# epic.net
KiCad netlist of a schematic drawn in Altium Designer
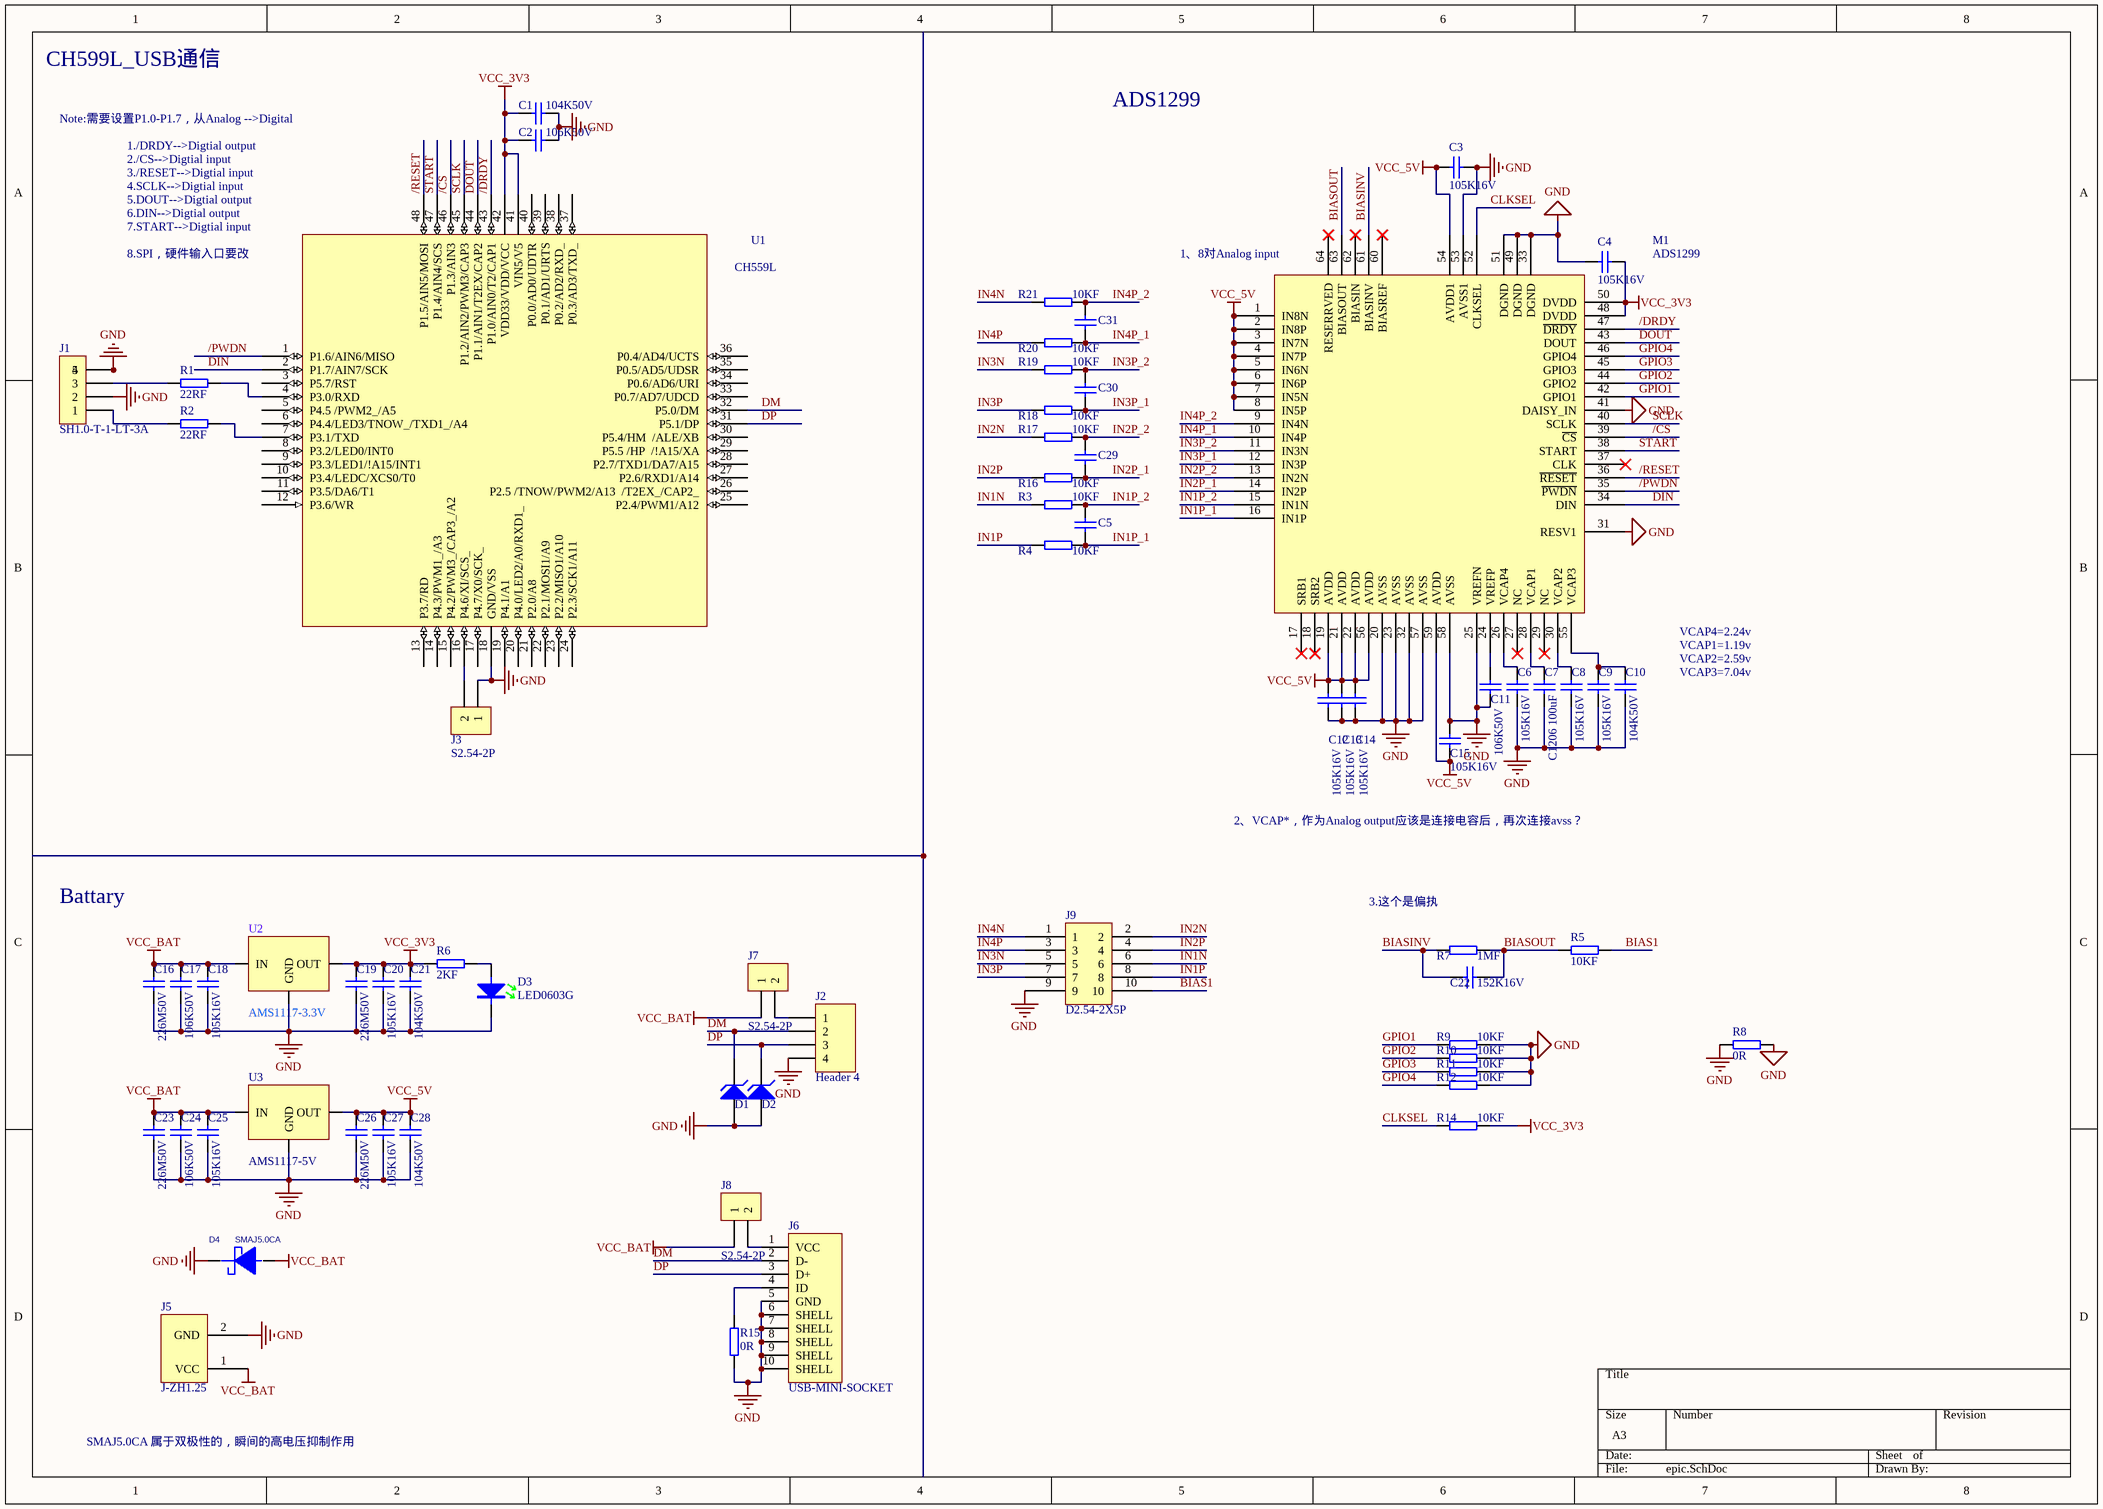
[diagram p0: epic.SchDoc]

(export (version "E")
  (design (tool "Eeschema 10.0.6"))
  (components
    (comp (ref "C1")
      (value "104K50V")
      (footprint "C0603")
      (description "贴片电容-陶瓷")
      (libsource (lib "Capacitor") (part "C0603X7R-104K50V"))
    )
    (comp (ref "C2")
      (value "106K50V")
      (footprint "C0603")
      (description "贴片电容-陶瓷")
      (libsource (lib "Capacitor") (part "C0603X7R-106K50V"))
    )
    (comp (ref "C3")
      (value "105K16V")
      (footprint "C0603")
      (description "贴片电容-陶瓷")
      (libsource (lib "Capacitor") (part "C0603X7R-105K16V"))
    )
    (comp (ref "C4")
      (value "105K16V")
      (footprint "C0603")
      (description "贴片电容-陶瓷")
      (libsource (lib "Capacitor") (part "C0603X7R-105K16V"))
    )
    (comp (ref "C5")
      (value "101K10V")
      (footprint "C0603")
      (description "贴片电容-陶瓷")
      (libsource (lib "Capacitor") (part "C0603X7R-101K10V"))
    )
    (comp (ref "C6")
      (value "105K16V")
      (footprint "C0603")
      (description "贴片电容-陶瓷")
      (libsource (lib "Capacitor") (part "C0603X7R-105K16V"))
    )
    (comp (ref "C7")
      (value "C1206 100uF")
      (footprint "C1206")
      (libsource (lib "Capacitor") (part "C1206钽电容 --100UF"))
    )
    (comp (ref "C8")
      (value "105K16V")
      (footprint "C0603")
      (description "贴片电容-陶瓷")
      (libsource (lib "Capacitor") (part "C0603X7R-105K16V"))
    )
    (comp (ref "C9")
      (value "105K16V")
      (footprint "C0603")
      (description "贴片电容-陶瓷")
      (libsource (lib "Capacitor") (part "C0603X7R-105K16V"))
    )
    (comp (ref "C10")
      (value "104K50V")
      (footprint "C0603")
      (description "贴片电容-陶瓷")
      (libsource (lib "Capacitor") (part "C0603X7R-104K50V"))
    )
    (comp (ref "C11")
      (value "106K50V")
      (footprint "C0603")
      (description "贴片电容-陶瓷")
      (libsource (lib "Capacitor") (part "C0603X7R-106K50V"))
    )
    (comp (ref "C12")
      (value "105K16V")
      (footprint "C0603")
      (description "贴片电容-陶瓷")
      (libsource (lib "Capacitor") (part "C0603X7R-105K16V"))
    )
    (comp (ref "C13")
      (value "105K16V")
      (footprint "C0603")
      (description "贴片电容-陶瓷")
      (libsource (lib "Capacitor") (part "C0603X7R-105K16V"))
    )
    (comp (ref "C14")
      (value "105K16V")
      (footprint "C0603")
      (description "贴片电容-陶瓷")
      (libsource (lib "Capacitor") (part "C0603X7R-105K16V"))
    )
    (comp (ref "C15")
      (value "105K16V")
      (footprint "C0603")
      (description "贴片电容-陶瓷")
      (libsource (lib "Capacitor") (part "C0603X7R-105K16V"))
    )
    (comp (ref "C16")
      (value "226M50V")
      (footprint "C0805")
      (description "贴片电容-陶瓷")
      (libsource (lib "aiwacV2.0") (part "C0805Y5V-226M50V"))
    )
    (comp (ref "C17")
      (value "106K50V")
      (footprint "C0603")
      (description "贴片电容-陶瓷")
      (libsource (lib "aiwacV2.0") (part "C0603X7R-106K50V"))
    )
    (comp (ref "C18")
      (value "105K16V")
      (footprint "C0603")
      (description "贴片电容-陶瓷")
      (libsource (lib "aiwacV2.0") (part "C0603X7R-105K16V"))
    )
    (comp (ref "C19")
      (value "226M50V")
      (footprint "C0805")
      (description "贴片电容-陶瓷")
      (libsource (lib "aiwacV2.0") (part "C0805Y5V-226M50V"))
    )
    (comp (ref "C20")
      (value "105K16V")
      (footprint "C0603")
      (description "贴片电容-陶瓷")
      (libsource (lib "aiwacV2.0") (part "C0603X7R-105K16V"))
    )
    (comp (ref "C21")
      (value "104K50V")
      (footprint "C0603")
      (description "贴片电容-陶瓷")
      (libsource (lib "Capacitor") (part "C0603X7R-104K50V"))
    )
    (comp (ref "C22")
      (value "152K16V")
      (footprint "C0603")
      (description "贴片电容-陶瓷")
      (libsource (lib "Capacitor") (part "C0603X7R-152K16V"))
    )
    (comp (ref "C23")
      (value "226M50V")
      (footprint "C0805")
      (description "贴片电容-陶瓷")
      (libsource (lib "aiwacV2.0") (part "C0805Y5V-226M50V"))
    )
    (comp (ref "C24")
      (value "106K50V")
      (footprint "C0603")
      (description "贴片电容-陶瓷")
      (libsource (lib "aiwacV2.0") (part "C0603X7R-106K50V"))
    )
    (comp (ref "C25")
      (value "105K16V")
      (footprint "C0603")
      (description "贴片电容-陶瓷")
      (libsource (lib "aiwacV2.0") (part "C0603X7R-105K16V"))
    )
    (comp (ref "C26")
      (value "226M50V")
      (footprint "C0805")
      (description "贴片电容-陶瓷")
      (libsource (lib "aiwacV2.0") (part "C0805Y5V-226M50V"))
    )
    (comp (ref "C27")
      (value "105K16V")
      (footprint "C0603")
      (description "贴片电容-陶瓷")
      (libsource (lib "aiwacV2.0") (part "C0603X7R-105K16V"))
    )
    (comp (ref "C28")
      (value "104K50V")
      (footprint "C0603")
      (description "贴片电容-陶瓷")
      (libsource (lib "Capacitor") (part "C0603X7R-104K50V"))
    )
    (comp (ref "C29")
      (value "101K10V")
      (footprint "C0603")
      (description "贴片电容-陶瓷")
      (libsource (lib "Capacitor") (part "C0603X7R-101K10V"))
    )
    (comp (ref "C30")
      (value "101K10V")
      (footprint "C0603")
      (description "贴片电容-陶瓷")
      (libsource (lib "Capacitor") (part "C0603X7R-101K10V"))
    )
    (comp (ref "C31")
      (value "101K10V")
      (footprint "C0603")
      (description "贴片电容-陶瓷")
      (libsource (lib "Capacitor") (part "C0603X7R-101K10V"))
    )
    (comp (ref "D1")
      (value "ESDA_TR1/0603")
      (footprint "HS_0603D")
      (description "Zener Diode")
      (fields (field (name "PUBLISHER") "*"))
      (libsource (lib "aiwacV2.0") (part "D Zener"))
    )
    (comp (ref "D2")
      (value "ESDA_TR1/0603")
      (footprint "HS_0603D")
      (description "Zener Diode")
      (fields (field (name "PUBLISHER") "*"))
      (libsource (lib "aiwacV2.0") (part "D Zener"))
    )
    (comp (ref "D3")
      (value "LED0603G")
      (footprint "D-LED0603G")
      (description "贴片二极管-LED")
      (libsource (lib "aiwacV2.0") (part "DLED-0603-G"))
    )
    (comp (ref "D4")
      (value "SMAJ5.0CA")
      (footprint "PCB11:DO-214")
      (libsource (lib "aiwacV2.0") (part "SMAJ5.0CA"))
    )
    (comp (ref "J1")
      (value "SH1.0-T-1-LT-3A")
      (footprint "AIWAC-TF_CARD-V02:J-SH1.0-T-1-LT-3A")
      (description "接插件-SH1.0-T-1-LT-3A")
      (libsource (lib "aiwacV2.0") (part "SH1.0-T-1-LT-3A"))
    )
    (comp (ref "J2")
      (value "Header 4")
      (footprint "USB-AB")
      (description "Header, 4-Pin")
      (fields (field (name "PUBLISHER") "Altium Limited"))
      (libsource (lib "aiwacV2.0") (part "Header 4"))
    )
    (comp (ref "J3")
      (value "S2.54-2P")
      (footprint "S2.54-2P")
      (description "单排排针-直针")
      (libsource (lib "") (part "J-S2.54-2P_1"))
    )
    (comp (ref "J5")
      (value "J-ZH1.25")
      (footprint "ZH1.25_2P")
      (libsource (lib "Connector") (part "J-ZH1.25"))
    )
    (comp (ref "J6")
      (value "USB-MINI-SOCKET")
      (footprint "MICRO-USB - 5.9")
      (description "USB-A卧式插座")
      (libsource (lib "PCB_Project_1") (part "J-USB-MINI-SOCKET"))
    )
    (comp (ref "J7")
      (value "S2.54-2P")
      (footprint "S2.54-2P")
      (description "单排排针-直针")
      (libsource (lib "Connector") (part "J-S2.54-2P"))
    )
    (comp (ref "J8")
      (value "S2.54-2P")
      (footprint "S2.54-2P")
      (description "单排排针-直针")
      (libsource (lib "Connector") (part "J-S2.54-2P"))
    )
    (comp (ref "J9")
      (value "D2.54-2X5P")
      (footprint "D2.54-2X5P")
      (description "双排排针-直针")
      (libsource (lib "Connector") (part "J-D2.54-2X5P"))
    )
    (comp (ref "M1")
      (value "ADS1299")
      (footprint "ADS1299-TSQFP50P1200X1200X105-64N")
      (description "ADS1299-S-PQFP-64")
      (libsource (lib "epic") (part "ADS1299"))
    )
    (comp (ref "R1")
      (value "22RF")
      (footprint "R0603")
      (description "贴片电阻-通用")
      (libsource (lib "Resistor") (part "R0603-22RF"))
    )
    (comp (ref "R2")
      (value "22RF")
      (footprint "R0603")
      (description "贴片电阻-通用")
      (libsource (lib "Resistor") (part "R0603-22RF"))
    )
    (comp (ref "R3")
      (value "10KF")
      (footprint "R0603")
      (description "贴片电阻-通用")
      (libsource (lib "Resistor") (part "R0603-10KF"))
    )
    (comp (ref "R4")
      (value "10KF")
      (footprint "R0603")
      (description "贴片电阻-通用")
      (libsource (lib "Resistor") (part "R0603-10KF"))
    )
    (comp (ref "R5")
      (value "10KF")
      (footprint "R0603")
      (description "贴片电阻-通用")
      (libsource (lib "Resistor") (part "R0603-10KF"))
    )
    (comp (ref "R6")
      (value "2KF")
      (footprint "R0603")
      (description "贴片电阻-通用")
      (libsource (lib "Resistor") (part "R0603-2KF"))
    )
    (comp (ref "R7")
      (value "1MF")
      (footprint "R0603")
      (description "贴片电阻-通用")
      (libsource (lib "Resistor") (part "R0603-1MF"))
    )
    (comp (ref "R8")
      (value "0R")
      (footprint "R0603")
      (description "贴片电阻-通用")
      (libsource (lib "Resistor") (part "R0603-0R"))
    )
    (comp (ref "R9")
      (value "10KF")
      (footprint "R0603")
      (description "贴片电阻-通用")
      (libsource (lib "Resistor") (part "R0603-10KF"))
    )
    (comp (ref "R10")
      (value "10KF")
      (footprint "R0603")
      (description "贴片电阻-通用")
      (libsource (lib "Resistor") (part "R0603-10KF"))
    )
    (comp (ref "R11")
      (value "10KF")
      (footprint "R0603")
      (description "贴片电阻-通用")
      (libsource (lib "Resistor") (part "R0603-10KF"))
    )
    (comp (ref "R12")
      (value "10KF")
      (footprint "R0603")
      (description "贴片电阻-通用")
      (libsource (lib "Resistor") (part "R0603-10KF"))
    )
    (comp (ref "R14")
      (value "10KF")
      (footprint "R0603")
      (description "贴片电阻-通用")
      (libsource (lib "Resistor") (part "R0603-10KF"))
    )
    (comp (ref "R15")
      (value "0R")
      (footprint "R0603")
      (description "贴片电阻-通用")
      (libsource (lib "Resistor") (part "R0603-0R"))
    )
    (comp (ref "R16")
      (value "10KF")
      (footprint "R0603")
      (description "贴片电阻-通用")
      (libsource (lib "Resistor") (part "R0603-10KF"))
    )
    (comp (ref "R17")
      (value "10KF")
      (footprint "R0603")
      (description "贴片电阻-通用")
      (libsource (lib "Resistor") (part "R0603-10KF"))
    )
    (comp (ref "R18")
      (value "10KF")
      (footprint "R0603")
      (description "贴片电阻-通用")
      (libsource (lib "Resistor") (part "R0603-10KF"))
    )
    (comp (ref "R19")
      (value "10KF")
      (footprint "R0603")
      (description "贴片电阻-通用")
      (libsource (lib "Resistor") (part "R0603-10KF"))
    )
    (comp (ref "R20")
      (value "10KF")
      (footprint "R0603")
      (description "贴片电阻-通用")
      (libsource (lib "Resistor") (part "R0603-10KF"))
    )
    (comp (ref "R21")
      (value "10KF")
      (footprint "R0603")
      (description "贴片电阻-通用")
      (libsource (lib "Resistor") (part "R0603-10KF"))
    )
    (comp (ref "U1")
      (value "CH559L")
      (footprint "LQFP48")
      (description "单片机")
      (libsource (lib "aiwacV2.0") (part "CH559L"))
    )
    (comp (ref "U2")
      (value "AMS1117-3.3V")
      (footprint "SOT-223")
      (description "芯片 电源类")
      (libsource (lib "aiwacV2.0") (part "AP1117-33 SOT-223"))
    )
    (comp (ref "U3")
      (value "AMS1117-5V")
      (footprint "SOT-223")
      (description "线性稳压器")
      (libsource (lib "epic") (part "AMS1117-5V"))
    )
  )
  (nets
    (net (code "1") (name "/BIAS1") (class "Default")
      (node (ref "J9") (pin "10") (pinfunction "10_10") (pintype "passive"))
      (node (ref "R5") (pin "2") (pinfunction "2_2") (pintype "passive"))
    )
    (net (code "2") (name "/BIASINV") (class "Default")
      (node (ref "C22") (pin "2") (pinfunction "2_2") (pintype "passive"))
      (node (ref "M1") (pin "61") (pinfunction "BIASINV_61") (pintype "passive"))
      (node (ref "R7") (pin "1") (pinfunction "1_1") (pintype "passive"))
    )
    (net (code "3") (name "/BIASOUT") (class "Default")
      (node (ref "C22") (pin "1") (pinfunction "1_1") (pintype "passive"))
      (node (ref "M1") (pin "63") (pinfunction "BIASOUT_63") (pintype "passive"))
      (node (ref "R5") (pin "1") (pinfunction "1_1") (pintype "passive"))
      (node (ref "R7") (pin "2") (pinfunction "2_2") (pintype "passive"))
    )
    (net (code "4") (name "/CLKSEL") (class "Default")
      (node (ref "M1") (pin "52") (pinfunction "CLKSEL_52") (pintype "passive"))
      (node (ref "R14") (pin "1") (pinfunction "1_1") (pintype "passive"))
    )
    (net (code "5") (name "/DIN") (class "Default")
      (node (ref "M1") (pin "34") (pinfunction "DIN_34") (pintype "passive"))
      (node (ref "U1") (pin "2") (pinfunction "P1.7/AIN7/SCK_2") (pintype "bidirectional"))
    )
    (net (code "6") (name "/DM") (class "Default")
      (node (ref "D1") (pin "2") (pinfunction "K_2") (pintype "passive"))
      (node (ref "J2") (pin "2") (pinfunction "2_2") (pintype "passive"))
      (node (ref "J6") (pin "2") (pinfunction "D-_2") (pintype "passive"))
      (node (ref "U1") (pin "32") (pinfunction "P5.0/DM_32") (pintype "bidirectional"))
    )
    (net (code "7") (name "/DOUT") (class "Default")
      (node (ref "M1") (pin "43") (pinfunction "DOUT_43") (pintype "passive"))
      (node (ref "U1") (pin "44") (pinfunction "P1.1/AIN1/T2EX/CAP2_44") (pintype "bidirectional"))
    )
    (net (code "8") (name "/DP") (class "Default")
      (node (ref "D2") (pin "2") (pinfunction "K_2") (pintype "passive"))
      (node (ref "J2") (pin "3") (pinfunction "3_3") (pintype "passive"))
      (node (ref "J6") (pin "3") (pinfunction "D+_3") (pintype "passive"))
      (node (ref "U1") (pin "31") (pinfunction "P5.1/DP_31") (pintype "bidirectional"))
    )
    (net (code "9") (name "/GPIO1") (class "Default")
      (node (ref "M1") (pin "42") (pinfunction "GPIO1_42") (pintype "passive"))
      (node (ref "R9") (pin "1") (pinfunction "1_1") (pintype "passive"))
    )
    (net (code "10") (name "/GPIO2") (class "Default")
      (node (ref "M1") (pin "44") (pinfunction "GPIO2_44") (pintype "passive"))
      (node (ref "R10") (pin "1") (pinfunction "1_1") (pintype "passive"))
    )
    (net (code "11") (name "/GPIO3") (class "Default")
      (node (ref "M1") (pin "45") (pinfunction "GPIO3_45") (pintype "passive"))
      (node (ref "R11") (pin "1") (pinfunction "1_1") (pintype "passive"))
    )
    (net (code "12") (name "/GPIO4") (class "Default")
      (node (ref "M1") (pin "46") (pinfunction "GPIO4_46") (pintype "passive"))
      (node (ref "R12") (pin "1") (pinfunction "1_1") (pintype "passive"))
    )
    (net (code "13") (name "/IN1N") (class "Default")
      (node (ref "J9") (pin "6") (pinfunction "6_6") (pintype "passive"))
      (node (ref "R3") (pin "1") (pinfunction "1_1") (pintype "passive"))
    )
    (net (code "14") (name "/IN1P") (class "Default")
      (node (ref "J9") (pin "8") (pinfunction "8_8") (pintype "passive"))
      (node (ref "R4") (pin "1") (pinfunction "1_1") (pintype "passive"))
    )
    (net (code "15") (name "/IN1P_1") (class "Default")
      (node (ref "C5") (pin "2") (pinfunction "2_2") (pintype "passive"))
      (node (ref "M1") (pin "16") (pinfunction "IN1P_16") (pintype "passive"))
      (node (ref "R4") (pin "2") (pinfunction "2_2") (pintype "passive"))
    )
    (net (code "16") (name "/IN1P_2") (class "Default")
      (node (ref "C5") (pin "1") (pinfunction "1_1") (pintype "passive"))
      (node (ref "M1") (pin "15") (pinfunction "IN1N_15") (pintype "passive"))
      (node (ref "R3") (pin "2") (pinfunction "2_2") (pintype "passive"))
    )
    (net (code "17") (name "/IN2N") (class "Default")
      (node (ref "J9") (pin "2") (pinfunction "2_2") (pintype "passive"))
      (node (ref "R17") (pin "1") (pinfunction "1_1") (pintype "passive"))
    )
    (net (code "18") (name "/IN2P") (class "Default")
      (node (ref "J9") (pin "4") (pinfunction "4_4") (pintype "passive"))
      (node (ref "R16") (pin "1") (pinfunction "1_1") (pintype "passive"))
    )
    (net (code "19") (name "/IN2P_1") (class "Default")
      (node (ref "C29") (pin "2") (pinfunction "2_2") (pintype "passive"))
      (node (ref "M1") (pin "14") (pinfunction "IN2P_14") (pintype "passive"))
      (node (ref "R16") (pin "2") (pinfunction "2_2") (pintype "passive"))
    )
    (net (code "20") (name "/IN2P_2") (class "Default")
      (node (ref "C29") (pin "1") (pinfunction "1_1") (pintype "passive"))
      (node (ref "M1") (pin "13") (pinfunction "IN2N_13") (pintype "passive"))
      (node (ref "R17") (pin "2") (pinfunction "2_2") (pintype "passive"))
    )
    (net (code "21") (name "/IN3N") (class "Default")
      (node (ref "J9") (pin "5") (pinfunction "5_5") (pintype "passive"))
      (node (ref "R19") (pin "1") (pinfunction "1_1") (pintype "passive"))
    )
    (net (code "22") (name "/IN3P") (class "Default")
      (node (ref "J9") (pin "7") (pinfunction "7_7") (pintype "passive"))
      (node (ref "R18") (pin "1") (pinfunction "1_1") (pintype "passive"))
    )
    (net (code "23") (name "/IN3P_1") (class "Default")
      (node (ref "C30") (pin "2") (pinfunction "2_2") (pintype "passive"))
      (node (ref "M1") (pin "12") (pinfunction "IN3P_12") (pintype "passive"))
      (node (ref "R18") (pin "2") (pinfunction "2_2") (pintype "passive"))
    )
    (net (code "24") (name "/IN3P_2") (class "Default")
      (node (ref "C30") (pin "1") (pinfunction "1_1") (pintype "passive"))
      (node (ref "M1") (pin "11") (pinfunction "IN3N_11") (pintype "passive"))
      (node (ref "R19") (pin "2") (pinfunction "2_2") (pintype "passive"))
    )
    (net (code "25") (name "/IN4N") (class "Default")
      (node (ref "J9") (pin "1") (pinfunction "1_1") (pintype "passive"))
      (node (ref "R21") (pin "1") (pinfunction "1_1") (pintype "passive"))
    )
    (net (code "26") (name "/IN4P") (class "Default")
      (node (ref "J9") (pin "3") (pinfunction "3_3") (pintype "passive"))
      (node (ref "R20") (pin "1") (pinfunction "1_1") (pintype "passive"))
    )
    (net (code "27") (name "/IN4P_1") (class "Default")
      (node (ref "C31") (pin "2") (pinfunction "2_2") (pintype "passive"))
      (node (ref "M1") (pin "10") (pinfunction "IN4P_10") (pintype "passive"))
      (node (ref "R20") (pin "2") (pinfunction "2_2") (pintype "passive"))
    )
    (net (code "28") (name "/IN4P_2") (class "Default")
      (node (ref "C31") (pin "1") (pinfunction "1_1") (pintype "passive"))
      (node (ref "M1") (pin "9") (pinfunction "IN4N_9") (pintype "passive"))
      (node (ref "R21") (pin "2") (pinfunction "2_2") (pintype "passive"))
    )
    (net (code "29") (name "/SCLK") (class "Default")
      (node (ref "M1") (pin "40") (pinfunction "SCLK_40") (pintype "passive"))
      (node (ref "U1") (pin "45") (pinfunction "P1.2/AIN2/PWM3/CAP3_45") (pintype "bidirectional"))
    )
    (net (code "30") (name "/START") (class "Default")
      (node (ref "M1") (pin "38") (pinfunction "START_38") (pintype "passive"))
      (node (ref "U1") (pin "47") (pinfunction "P1.4/AIN4/SCS_47") (pintype "bidirectional"))
    )
    (net (code "31") (name "/{slash}CS") (class "Default")
      (node (ref "M1") (pin "39") (pinfunction "~{CS}_39") (pintype "passive"))
      (node (ref "U1") (pin "46") (pinfunction "P1.3/AIN3_46") (pintype "bidirectional"))
    )
    (net (code "32") (name "/{slash}DRDY") (class "Default")
      (node (ref "M1") (pin "47") (pinfunction "~{DRDY}_47") (pintype "passive"))
      (node (ref "U1") (pin "43") (pinfunction "P1.0/AIN0/T2/CAP1_43") (pintype "bidirectional"))
    )
    (net (code "33") (name "/{slash}PWDN") (class "Default")
      (node (ref "M1") (pin "35") (pinfunction "~{PWDN}_35") (pintype "passive"))
      (node (ref "U1") (pin "1") (pinfunction "P1.6/AIN6/MISO_1") (pintype "bidirectional"))
    )
    (net (code "34") (name "/{slash}RESET") (class "Default")
      (node (ref "M1") (pin "36") (pinfunction "~{RESET}_36") (pintype "passive"))
      (node (ref "U1") (pin "48") (pinfunction "P1.5/AIN5/MOSI_48") (pintype "bidirectional"))
    )
    (net (code "35") (name "GND") (class "Default")
      (node (ref "C1") (pin "1") (pinfunction "1_1") (pintype "passive"))
      (node (ref "C10") (pin "1") (pinfunction "1_1") (pintype "passive"))
      (node (ref "C11") (pin "1") (pinfunction "1_1") (pintype "passive"))
      (node (ref "C12") (pin "2") (pinfunction "2_2") (pintype "passive"))
      (node (ref "C13") (pin "2") (pinfunction "2_2") (pintype "passive"))
      (node (ref "C14") (pin "2") (pinfunction "2_2") (pintype "passive"))
      (node (ref "C15") (pin "2") (pinfunction "2_2") (pintype "passive"))
      (node (ref "C16") (pin "2") (pinfunction "2_2") (pintype "passive"))
      (node (ref "C17") (pin "2") (pinfunction "2_2") (pintype "passive"))
      (node (ref "C18") (pin "2") (pinfunction "2_2") (pintype "passive"))
      (node (ref "C19") (pin "2") (pinfunction "2_2") (pintype "passive"))
      (node (ref "C2") (pin "1") (pinfunction "1_1") (pintype "passive"))
      (node (ref "C20") (pin "2") (pinfunction "2_2") (pintype "passive"))
      (node (ref "C21") (pin "1") (pinfunction "1_1") (pintype "passive"))
      (node (ref "C23") (pin "2") (pinfunction "2_2") (pintype "passive"))
      (node (ref "C24") (pin "2") (pinfunction "2_2") (pintype "passive"))
      (node (ref "C25") (pin "2") (pinfunction "2_2") (pintype "passive"))
      (node (ref "C26") (pin "2") (pinfunction "2_2") (pintype "passive"))
      (node (ref "C27") (pin "2") (pinfunction "2_2") (pintype "passive"))
      (node (ref "C28") (pin "1") (pinfunction "1_1") (pintype "passive"))
      (node (ref "C3") (pin "1") (pinfunction "1_1") (pintype "passive"))
      (node (ref "C4") (pin "1") (pinfunction "1_1") (pintype "passive"))
      (node (ref "C6") (pin "2") (pinfunction "2_2") (pintype "passive"))
      (node (ref "C7") (pin "1") (pinfunction "1_1") (pintype "passive"))
      (node (ref "C8") (pin "2") (pinfunction "2_2") (pintype "passive"))
      (node (ref "C9") (pin "2") (pinfunction "2_2") (pintype "passive"))
      (node (ref "D1") (pin "1") (pinfunction "A_1") (pintype "passive"))
      (node (ref "D2") (pin "1") (pinfunction "A_1") (pintype "passive"))
      (node (ref "D3") (pin "2") (pinfunction "2_2") (pintype "passive"))
      (node (ref "D4") (pin "2") (pinfunction "-_2") (pintype "passive"))
      (node (ref "J1") (pin "2") (pinfunction "2_2") (pintype "passive"))
      (node (ref "J1") (pin "4") (pinfunction "4_4") (pintype "passive"))
      (node (ref "J1") (pin "5") (pinfunction "5_5") (pintype "passive"))
      (node (ref "J2") (pin "4") (pinfunction "4_4") (pintype "passive"))
      (node (ref "J3") (pin "1") (pinfunction "1_1") (pintype "passive"))
      (node (ref "J5") (pin "2") (pinfunction "GND_2") (pintype "power_in"))
      (node (ref "J6") (pin "10") (pinfunction "SHELL_10") (pintype "passive"))
      (node (ref "J6") (pin "5") (pinfunction "GND_5") (pintype "passive"))
      (node (ref "J6") (pin "6") (pinfunction "SHELL_6") (pintype "passive"))
      (node (ref "J6") (pin "7") (pinfunction "SHELL_7") (pintype "passive"))
      (node (ref "J6") (pin "8") (pinfunction "SHELL_8") (pintype "passive"))
      (node (ref "J6") (pin "9") (pinfunction "SHELL_9") (pintype "passive"))
      (node (ref "J9") (pin "9") (pinfunction "9_9") (pintype "passive"))
      (node (ref "M1") (pin "20") (pinfunction "AVSS_20") (pintype "passive"))
      (node (ref "M1") (pin "23") (pinfunction "AVSS_23") (pintype "passive"))
      (node (ref "M1") (pin "25") (pinfunction "VREFN_25") (pintype "passive"))
      (node (ref "M1") (pin "31") (pinfunction "RESV1_31") (pintype "passive"))
      (node (ref "M1") (pin "32") (pinfunction "AVSS_32") (pintype "passive"))
      (node (ref "M1") (pin "33") (pinfunction "DGND_33") (pintype "passive"))
      (node (ref "M1") (pin "41") (pinfunction "DAISY_IN_41") (pintype "passive"))
      (node (ref "M1") (pin "49") (pinfunction "DGND_49") (pintype "passive"))
      (node (ref "M1") (pin "51") (pinfunction "DGND_51") (pintype "passive"))
      (node (ref "M1") (pin "53") (pinfunction "AVSS1_53") (pintype "passive"))
      (node (ref "M1") (pin "57") (pinfunction "AVSS_57") (pintype "passive"))
      (node (ref "M1") (pin "58") (pinfunction "AVSS_58") (pintype "passive"))
      (node (ref "R10") (pin "2") (pinfunction "2_2") (pintype "passive"))
      (node (ref "R11") (pin "2") (pinfunction "2_2") (pintype "passive"))
      (node (ref "R12") (pin "2") (pinfunction "2_2") (pintype "passive"))
      (node (ref "R15") (pin "1") (pinfunction "1_1") (pintype "passive"))
      (node (ref "R8") (pin "1") (pinfunction "1_1") (pintype "passive"))
      (node (ref "R8") (pin "2") (pinfunction "2_2") (pintype "passive"))
      (node (ref "R9") (pin "2") (pinfunction "2_2") (pintype "passive"))
      (node (ref "U1") (pin "18") (pinfunction "GND/VSS_18") (pintype "passive"))
      (node (ref "U2") (pin "1") (pinfunction "GND_1") (pintype "passive"))
      (node (ref "U3") (pin "1") (pinfunction "GND_1") (pintype "passive"))
    )
    (net (code "36") (name "Net-(D3-Pad1)") (class "Default")
      (node (ref "D3") (pin "1") (pinfunction "1_1") (pintype "passive"))
      (node (ref "R6") (pin "2") (pinfunction "2_2") (pintype "passive"))
    )
    (net (code "37") (name "Net-(J1-Pad1)") (class "Default")
      (node (ref "J1") (pin "1") (pinfunction "1_1") (pintype "passive"))
      (node (ref "R2") (pin "1") (pinfunction "1_1") (pintype "passive"))
    )
    (net (code "38") (name "Net-(J1-Pad3)") (class "Default")
      (node (ref "J1") (pin "3") (pinfunction "3_3") (pintype "passive"))
      (node (ref "R1") (pin "1") (pinfunction "1_1") (pintype "passive"))
    )
    (net (code "39") (name "Net-(J2-Pad1)") (class "Default")
      (node (ref "J2") (pin "1") (pinfunction "1_1") (pintype "passive"))
      (node (ref "J7") (pin "2") (pinfunction "2_2") (pintype "passive"))
    )
    (net (code "40") (name "Net-(J6-ID)") (class "Default")
      (node (ref "J6") (pin "4") (pinfunction "ID_4") (pintype "passive"))
      (node (ref "R15") (pin "2") (pinfunction "2_2") (pintype "passive"))
    )
    (net (code "41") (name "Net-(J6-VCC)") (class "Default")
      (node (ref "J6") (pin "1") (pinfunction "VCC_1") (pintype "passive"))
      (node (ref "J8") (pin "2") (pinfunction "2_2") (pintype "passive"))
    )
    (net (code "42") (name "Net-(M1-VCAP1)") (class "Default")
      (node (ref "C7") (pin "2") (pinfunction "2_2") (pintype "passive"))
      (node (ref "M1") (pin "28") (pinfunction "VCAP1_28") (pintype "passive"))
    )
    (net (code "43") (name "Net-(M1-VCAP2)") (class "Default")
      (node (ref "C8") (pin "1") (pinfunction "1_1") (pintype "passive"))
      (node (ref "M1") (pin "30") (pinfunction "VCAP2_30") (pintype "passive"))
    )
    (net (code "44") (name "Net-(M1-VCAP3)") (class "Default")
      (node (ref "C10") (pin "2") (pinfunction "2_2") (pintype "passive"))
      (node (ref "C9") (pin "1") (pinfunction "1_1") (pintype "passive"))
      (node (ref "M1") (pin "55") (pinfunction "VCAP3_55") (pintype "passive"))
    )
    (net (code "45") (name "Net-(M1-VCAP4)") (class "Default")
      (node (ref "C6") (pin "1") (pinfunction "1_1") (pintype "passive"))
      (node (ref "M1") (pin "26") (pinfunction "VCAP4_26") (pintype "passive"))
    )
    (net (code "46") (name "Net-(M1-VREFP)") (class "Default")
      (node (ref "C11") (pin "2") (pinfunction "2_2") (pintype "passive"))
      (node (ref "M1") (pin "24") (pinfunction "VREFP_24") (pintype "passive"))
    )
    (net (code "47") (name "Net-(U1-P3.0{slash}RXD)") (class "Default")
      (node (ref "R1") (pin "2") (pinfunction "2_2") (pintype "passive"))
      (node (ref "U1") (pin "4") (pinfunction "P3.0/RXD_4") (pintype "bidirectional"))
    )
    (net (code "48") (name "Net-(U1-P3.1{slash}TXD)") (class "Default")
      (node (ref "R2") (pin "2") (pinfunction "2_2") (pintype "passive"))
      (node (ref "U1") (pin "7") (pinfunction "P3.1/TXD_7") (pintype "bidirectional"))
    )
    (net (code "49") (name "Net-(U1-P4.6{slash}XI{slash}SCS_)") (class "Default")
      (node (ref "J3") (pin "2") (pinfunction "2_2") (pintype "passive"))
      (node (ref "U1") (pin "16") (pinfunction "P4.6/XI/SCS__16") (pintype "bidirectional"))
    )
    (net (code "50") (name "VCC_3V3") (class "Default")
      (node (ref "C1") (pin "2") (pinfunction "2_2") (pintype "passive"))
      (node (ref "C19") (pin "1") (pinfunction "1_1") (pintype "passive"))
      (node (ref "C2") (pin "2") (pinfunction "2_2") (pintype "passive"))
      (node (ref "C20") (pin "1") (pinfunction "1_1") (pintype "passive"))
      (node (ref "C21") (pin "2") (pinfunction "2_2") (pintype "passive"))
      (node (ref "C4") (pin "2") (pinfunction "2_2") (pintype "passive"))
      (node (ref "M1") (pin "48") (pinfunction "DVDD_48") (pintype "passive"))
      (node (ref "M1") (pin "50") (pinfunction "DVDD_50") (pintype "passive"))
      (node (ref "R14") (pin "2") (pinfunction "2_2") (pintype "passive"))
      (node (ref "R6") (pin "1") (pinfunction "1_1") (pintype "passive"))
      (node (ref "U1") (pin "41") (pinfunction "VIN5/V5_41") (pintype "passive"))
      (node (ref "U1") (pin "42") (pinfunction "VDD33/VDD/VCC_42") (pintype "passive"))
      (node (ref "U2") (pin "2") (pinfunction "OUT_2") (pintype "passive"))
    )
    (net (code "51") (name "VCC_5V") (class "Default")
      (node (ref "C12") (pin "1") (pinfunction "1_1") (pintype "passive"))
      (node (ref "C13") (pin "1") (pinfunction "1_1") (pintype "passive"))
      (node (ref "C14") (pin "1") (pinfunction "1_1") (pintype "passive"))
      (node (ref "C15") (pin "1") (pinfunction "1_1") (pintype "passive"))
      (node (ref "C26") (pin "1") (pinfunction "1_1") (pintype "passive"))
      (node (ref "C27") (pin "1") (pinfunction "1_1") (pintype "passive"))
      (node (ref "C28") (pin "2") (pinfunction "2_2") (pintype "passive"))
      (node (ref "C3") (pin "2") (pinfunction "2_2") (pintype "passive"))
      (node (ref "M1") (pin "1") (pinfunction "IN8N_1") (pintype "passive"))
      (node (ref "M1") (pin "19") (pinfunction "AVDD_19") (pintype "passive"))
      (node (ref "M1") (pin "2") (pinfunction "IN8P_2") (pintype "passive"))
      (node (ref "M1") (pin "21") (pinfunction "AVDD_21") (pintype "passive"))
      (node (ref "M1") (pin "22") (pinfunction "AVDD_22") (pintype "passive"))
      (node (ref "M1") (pin "3") (pinfunction "IN7N_3") (pintype "passive"))
      (node (ref "M1") (pin "4") (pinfunction "IN7P_4") (pintype "passive"))
      (node (ref "M1") (pin "5") (pinfunction "IN6N_5") (pintype "passive"))
      (node (ref "M1") (pin "54") (pinfunction "AVDD1_54") (pintype "passive"))
      (node (ref "M1") (pin "56") (pinfunction "AVDD_56") (pintype "passive"))
      (node (ref "M1") (pin "59") (pinfunction "AVDD_59") (pintype "passive"))
      (node (ref "M1") (pin "6") (pinfunction "IN6P_6") (pintype "passive"))
      (node (ref "M1") (pin "7") (pinfunction "IN5N_7") (pintype "passive"))
      (node (ref "M1") (pin "8") (pinfunction "IN5P_8") (pintype "passive"))
      (node (ref "U3") (pin "2") (pinfunction "OUT_2") (pintype "passive"))
    )
    (net (code "52") (name "VCC_BAT") (class "Default")
      (node (ref "C16") (pin "1") (pinfunction "1_1") (pintype "passive"))
      (node (ref "C17") (pin "1") (pinfunction "1_1") (pintype "passive"))
      (node (ref "C18") (pin "1") (pinfunction "1_1") (pintype "passive"))
      (node (ref "C23") (pin "1") (pinfunction "1_1") (pintype "passive"))
      (node (ref "C24") (pin "1") (pinfunction "1_1") (pintype "passive"))
      (node (ref "C25") (pin "1") (pinfunction "1_1") (pintype "passive"))
      (node (ref "D4") (pin "1") (pinfunction "+_1") (pintype "passive"))
      (node (ref "J5") (pin "1") (pinfunction "VCC_1") (pintype "power_in"))
      (node (ref "J7") (pin "1") (pinfunction "1_1") (pintype "passive"))
      (node (ref "J8") (pin "1") (pinfunction "1_1") (pintype "passive"))
      (node (ref "U2") (pin "3") (pinfunction "IN_3") (pintype "passive"))
      (node (ref "U3") (pin "3") (pinfunction "IN_3") (pintype "passive"))
    )
    (net (code "53") (name "unconnected-(M1-BIASIN-Pad62)") (class "Default")
      (node (ref "M1") (pin "62") (pinfunction "BIASIN_62") (pintype "passive+no_connect"))
    )
    (net (code "54") (name "unconnected-(M1-BIASREF-Pad60)") (class "Default")
      (node (ref "M1") (pin "60") (pinfunction "BIASREF_60") (pintype "passive+no_connect"))
    )
    (net (code "55") (name "unconnected-(M1-CLK-Pad37)") (class "Default")
      (node (ref "M1") (pin "37") (pinfunction "CLK_37") (pintype "passive+no_connect"))
    )
    (net (code "56") (name "unconnected-(M1-NC-Pad27)") (class "Default")
      (node (ref "M1") (pin "27") (pinfunction "NC_27") (pintype "passive+no_connect"))
    )
    (net (code "57") (name "unconnected-(M1-NC-Pad29)") (class "Default")
      (node (ref "M1") (pin "29") (pinfunction "NC_29") (pintype "passive+no_connect"))
    )
    (net (code "58") (name "unconnected-(M1-RESERRVED-Pad64)") (class "Default")
      (node (ref "M1") (pin "64") (pinfunction "RESERRVED_64") (pintype "passive+no_connect"))
    )
    (net (code "59") (name "unconnected-(M1-SRB1-Pad17)") (class "Default")
      (node (ref "M1") (pin "17") (pinfunction "SRB1_17") (pintype "passive+no_connect"))
    )
    (net (code "60") (name "unconnected-(M1-SRB2-Pad18)") (class "Default")
      (node (ref "M1") (pin "18") (pinfunction "SRB2_18") (pintype "passive+no_connect"))
    )
    (net (code "61") (name "unconnected-(U1-P0.0{slash}AD0{slash}UDTR-Pad40)") (class "Default")
      (node (ref "U1") (pin "40") (pinfunction "P0.0/AD0/UDTR_40") (pintype "bidirectional"))
    )
    (net (code "62") (name "unconnected-(U1-P0.1{slash}AD1{slash}URTS-Pad39)") (class "Default")
      (node (ref "U1") (pin "39") (pinfunction "P0.1/AD1/URTS_39") (pintype "bidirectional"))
    )
    (net (code "63") (name "unconnected-(U1-P0.2{slash}AD2{slash}RXD_-Pad38)") (class "Default")
      (node (ref "U1") (pin "38") (pinfunction "P0.2/AD2/RXD__38") (pintype "bidirectional"))
    )
    (net (code "64") (name "unconnected-(U1-P0.3{slash}AD3{slash}TXD_-Pad37)") (class "Default")
      (node (ref "U1") (pin "37") (pinfunction "P0.3/AD3/TXD__37") (pintype "bidirectional"))
    )
    (net (code "65") (name "unconnected-(U1-P0.4{slash}AD4{slash}UCTS-Pad36)") (class "Default")
      (node (ref "U1") (pin "36") (pinfunction "P0.4/AD4/UCTS_36") (pintype "bidirectional"))
    )
    (net (code "66") (name "unconnected-(U1-P0.5{slash}AD5{slash}UDSR-Pad35)") (class "Default")
      (node (ref "U1") (pin "35") (pinfunction "P0.5/AD5/UDSR_35") (pintype "bidirectional"))
    )
    (net (code "67") (name "unconnected-(U1-P0.6{slash}AD6{slash}URI-Pad34)") (class "Default")
      (node (ref "U1") (pin "34") (pinfunction "P0.6/AD6/URI_34") (pintype "bidirectional"))
    )
    (net (code "68") (name "unconnected-(U1-P0.7{slash}AD7{slash}UDCD-Pad33)") (class "Default")
      (node (ref "U1") (pin "33") (pinfunction "P0.7/AD7/UDCD_33") (pintype "bidirectional"))
    )
    (net (code "69") (name "unconnected-(U1-P2.0{slash}A8-Pad21)") (class "Default")
      (node (ref "U1") (pin "21") (pinfunction "P2.0/A8_21") (pintype "bidirectional"))
    )
    (net (code "70") (name "unconnected-(U1-P2.1{slash}MOSI1{slash}A9-Pad22)") (class "Default")
      (node (ref "U1") (pin "22") (pinfunction "P2.1/MOSI1/A9_22") (pintype "bidirectional"))
    )
    (net (code "71") (name "unconnected-(U1-P2.2{slash}MISO1{slash}A10-Pad23)") (class "Default")
      (node (ref "U1") (pin "23") (pinfunction "P2.2/MISO1/A10_23") (pintype "bidirectional"))
    )
    (net (code "72") (name "unconnected-(U1-P2.3{slash}SCK1{slash}A11-Pad24)") (class "Default")
      (node (ref "U1") (pin "24") (pinfunction "P2.3/SCK1/A11_24") (pintype "bidirectional"))
    )
    (net (code "73") (name "unconnected-(U1-P2.4{slash}PWM1{slash}A12-Pad25)") (class "Default")
      (node (ref "U1") (pin "25") (pinfunction "P2.4/PWM1/A12_25") (pintype "bidirectional"))
    )
    (net (code "74") (name "unconnected-(U1-P2.5_{slash}TNOW{slash}PWM2{slash}A13__{slash}T2EX_{slash}CAP2_-Pad26)") (class "Default")
      (node (ref "U1") (pin "26") (pinfunction "P2.5_/TNOW/PWM2/A13__/T2EX_/CAP2__26") (pintype "bidirectional"))
    )
    (net (code "75") (name "unconnected-(U1-P2.6{slash}RXD1{slash}A14-Pad27)") (class "Default")
      (node (ref "U1") (pin "27") (pinfunction "P2.6/RXD1/A14_27") (pintype "bidirectional"))
    )
    (net (code "76") (name "unconnected-(U1-P2.7{slash}TXD1{slash}DA7{slash}A15-Pad28)") (class "Default")
      (node (ref "U1") (pin "28") (pinfunction "P2.7/TXD1/DA7/A15_28") (pintype "bidirectional"))
    )
    (net (code "77") (name "unconnected-(U1-P3.2{slash}LED0{slash}INT0-Pad8)") (class "Default")
      (node (ref "U1") (pin "8") (pinfunction "P3.2/LED0/INT0_8") (pintype "bidirectional"))
    )
    (net (code "78") (name "unconnected-(U1-P3.3{slash}LED1{slash}!A15{slash}INT1-Pad9)") (class "Default")
      (node (ref "U1") (pin "9") (pinfunction "P3.3/LED1/!A15/INT1_9") (pintype "bidirectional"))
    )
    (net (code "79") (name "unconnected-(U1-P3.4{slash}LEDC{slash}XCS0{slash}T0-Pad10)") (class "Default")
      (node (ref "U1") (pin "10") (pinfunction "P3.4/LEDC/XCS0/T0_10") (pintype "bidirectional"))
    )
    (net (code "80") (name "unconnected-(U1-P3.5{slash}DA6{slash}T1-Pad11)") (class "Default")
      (node (ref "U1") (pin "11") (pinfunction "P3.5/DA6/T1_11") (pintype "bidirectional"))
    )
    (net (code "81") (name "unconnected-(U1-P3.6{slash}WR-Pad12)") (class "Default")
      (node (ref "U1") (pin "12") (pinfunction "P3.6/WR_12") (pintype "input"))
    )
    (net (code "82") (name "unconnected-(U1-P3.7{slash}RD-Pad13)") (class "Default")
      (node (ref "U1") (pin "13") (pinfunction "P3.7/RD_13") (pintype "bidirectional"))
    )
    (net (code "83") (name "unconnected-(U1-P4.0{slash}LED2{slash}A0{slash}RXD1_-Pad20)") (class "Default")
      (node (ref "U1") (pin "20") (pinfunction "P4.0/LED2/A0/RXD1__20") (pintype "bidirectional"))
    )
    (net (code "84") (name "unconnected-(U1-P4.1{slash}A1-Pad19)") (class "Default")
      (node (ref "U1") (pin "19") (pinfunction "P4.1/A1_19") (pintype "bidirectional"))
    )
    (net (code "85") (name "unconnected-(U1-P4.2{slash}PWM3_{slash}CAP3_{slash}A2-Pad15)") (class "Default")
      (node (ref "U1") (pin "15") (pinfunction "P4.2/PWM3_/CAP3_/A2_15") (pintype "bidirectional"))
    )
    (net (code "86") (name "unconnected-(U1-P4.3{slash}PWM1_{slash}A3-Pad14)") (class "Default")
      (node (ref "U1") (pin "14") (pinfunction "P4.3/PWM1_/A3_14") (pintype "bidirectional"))
    )
    (net (code "87") (name "unconnected-(U1-P4.4{slash}LED3{slash}TNOW_{slash}TXD1_{slash}A4-Pad6)") (class "Default")
      (node (ref "U1") (pin "6") (pinfunction "P4.4/LED3/TNOW_/TXD1_/A4_6") (pintype "bidirectional"))
    )
    (net (code "88") (name "unconnected-(U1-P4.5_{slash}PWM2_{slash}A5-Pad5)") (class "Default")
      (node (ref "U1") (pin "5") (pinfunction "P4.5_/PWM2_/A5_5") (pintype "bidirectional"))
    )
    (net (code "89") (name "unconnected-(U1-P4.7{slash}X0{slash}SCK_-Pad17)") (class "Default")
      (node (ref "U1") (pin "17") (pinfunction "P4.7/X0/SCK__17") (pintype "bidirectional"))
    )
    (net (code "90") (name "unconnected-(U1-P5.4{slash}HM__{slash}ALE{slash}XB-Pad30)") (class "Default")
      (node (ref "U1") (pin "30") (pinfunction "P5.4/HM__/ALE/XB_30") (pintype "bidirectional"))
    )
    (net (code "91") (name "unconnected-(U1-P5.5_{slash}HP__{slash}!A15{slash}XA-Pad29)") (class "Default")
      (node (ref "U1") (pin "29") (pinfunction "P5.5_/HP__/!A15/XA_29") (pintype "bidirectional"))
    )
    (net (code "92") (name "unconnected-(U1-P5.7{slash}RST-Pad3)") (class "Default")
      (node (ref "U1") (pin "3") (pinfunction "P5.7/RST_3") (pintype "bidirectional"))
    )
  )
)
